# SuperTester-v07.net
KiCad netlist of a schematic drawn in EAGLE
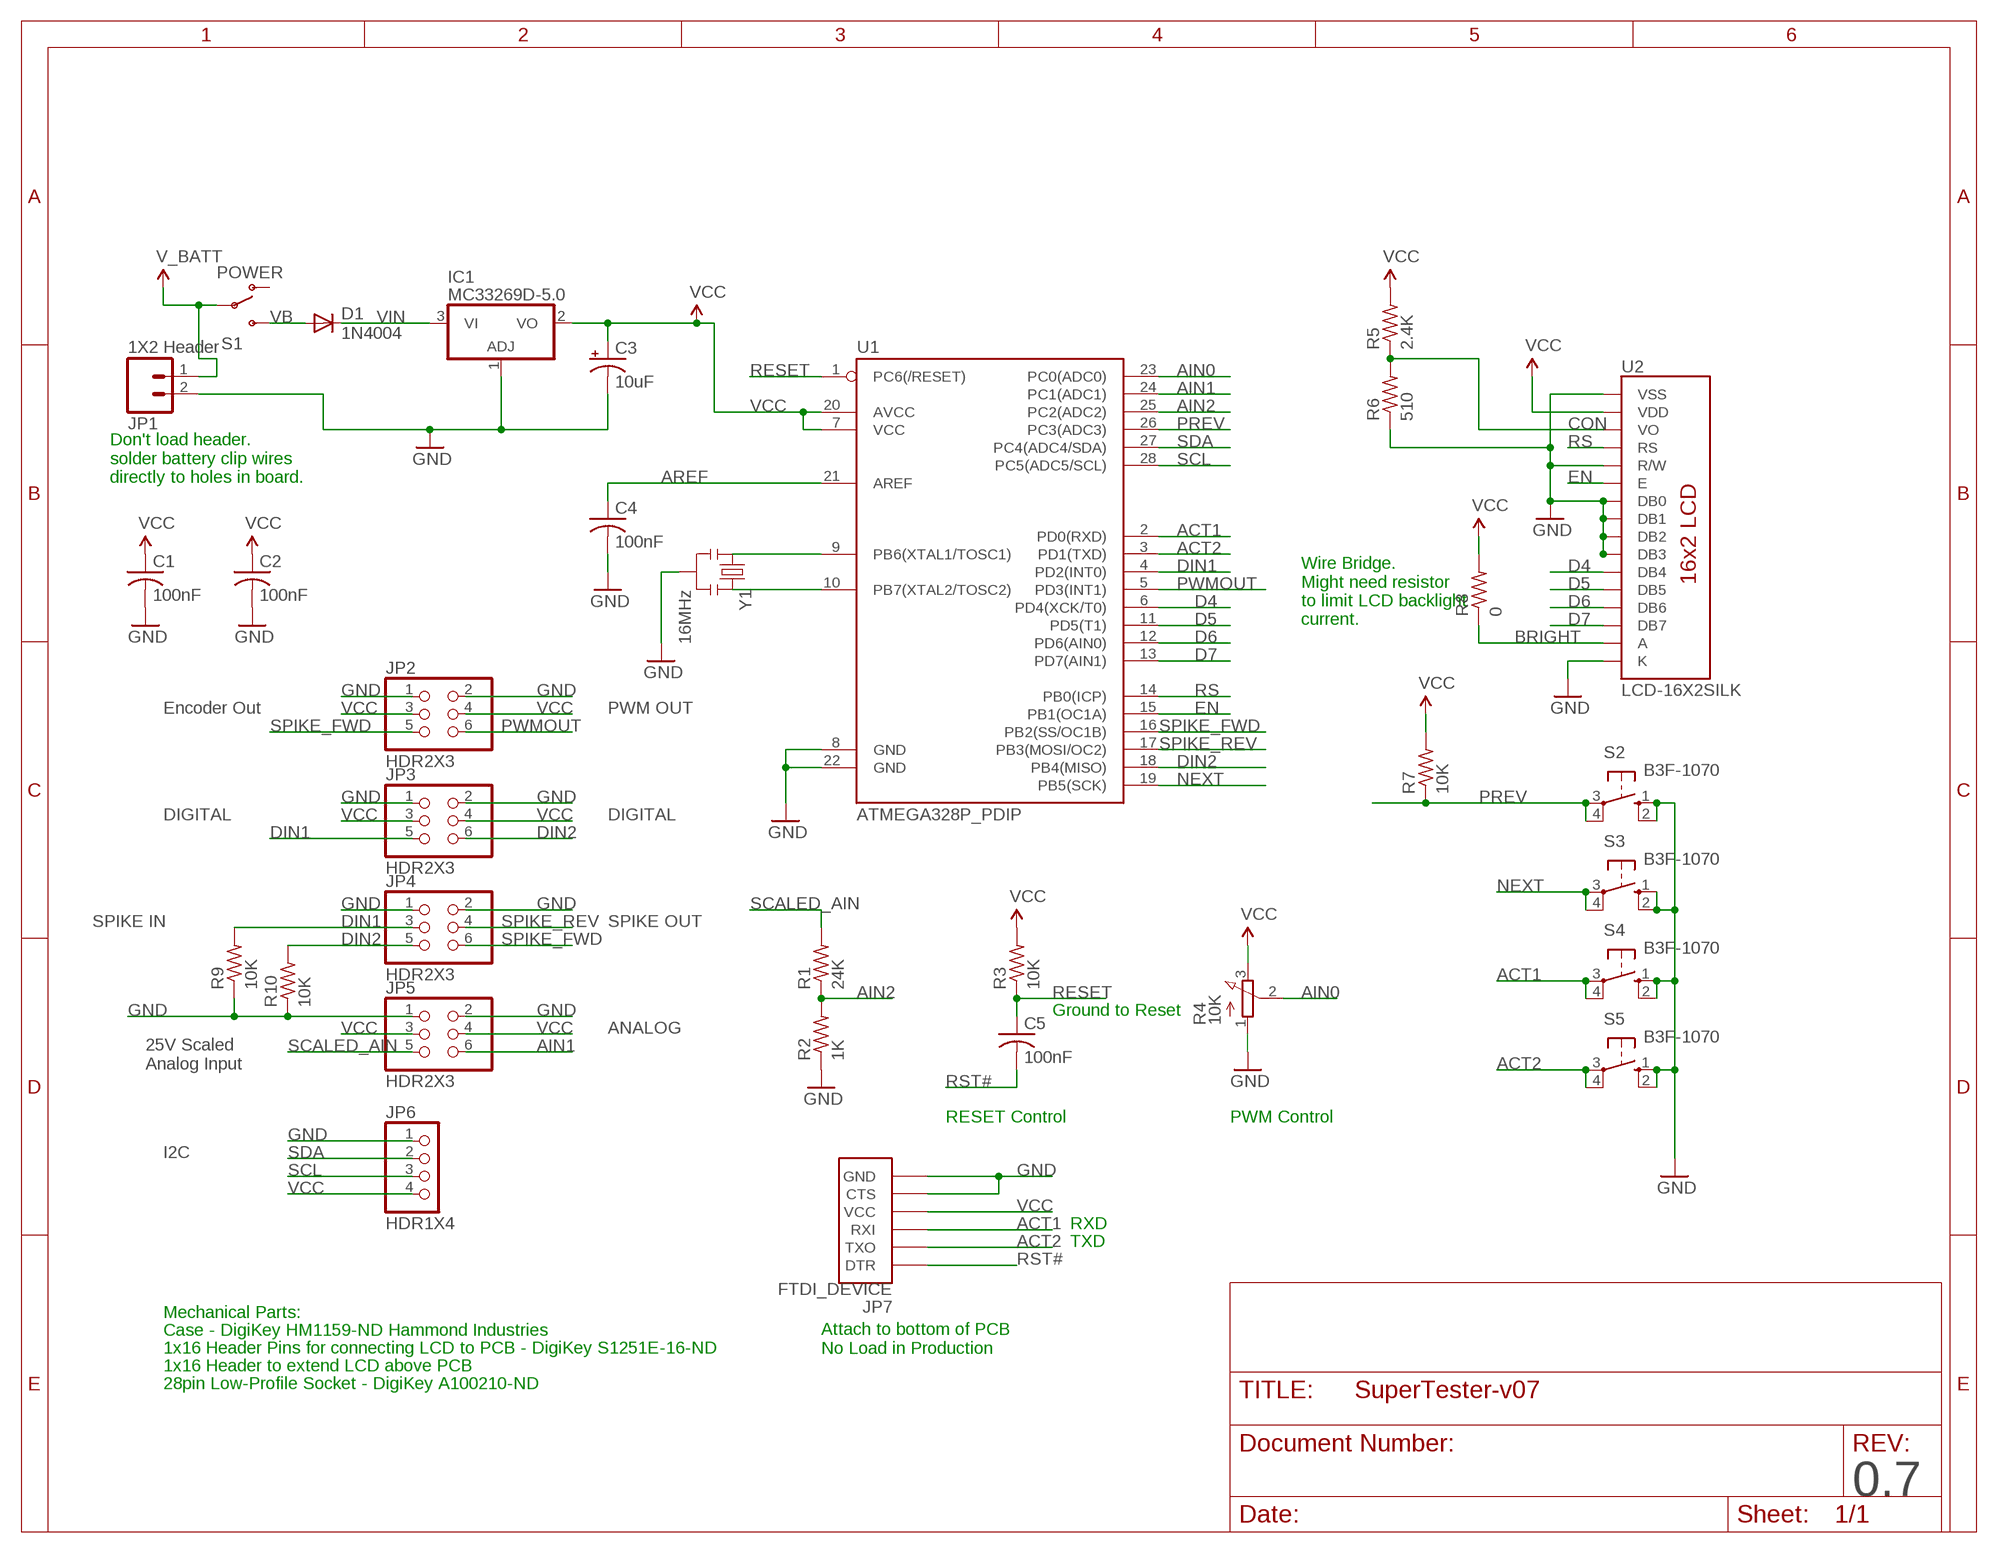
[diagram p0: schematic, sheet 1]

(export (version "E")
  (design (tool "Eeschema 10.0.6"))
  (components
    (comp (ref "C1")
      (value "100nF")
      (footprint "eagle-import:C025-025X050")
      (fields (field (name "PARTNO") "SR295E104MAR"))
      (libsource (lib "eagle-import") (part "C-US025-025X050"))
    )
    (comp (ref "C2")
      (value "100nF")
      (footprint "eagle-import:C025-025X050")
      (fields (field (name "PARTNO") "SR295E104MAR"))
      (libsource (lib "eagle-import") (part "C-US025-025X050"))
    )
    (comp (ref "C3")
      (value "10uF")
      (footprint "eagle-import:E2,5-6E")
      (fields (field (name "PARTNO") "TAP106M025SCS"))
      (libsource (lib "eagle-import") (part "CPOL-USE2,5-6E"))
    )
    (comp (ref "C4")
      (value "100nF")
      (footprint "eagle-import:C025-025X050")
      (fields (field (name "PARTNO") "SR295E104MAR"))
      (libsource (lib "eagle-import") (part "C-US025-025X050"))
    )
    (comp (ref "C5")
      (value "100nF")
      (footprint "eagle-import:C025-025X050")
      (fields (field (name "PARTNO") "SR295E104MAR"))
      (libsource (lib "eagle-import") (part "C-US025-025X050"))
    )
    (comp (ref "D1")
      (value "1N4004")
      (footprint "eagle-import:DO41-10")
      (fields (field (name "PARTNO") "1N4004GP-E3/54"))
      (libsource (lib "eagle-import") (part "1N4004"))
    )
    (comp (ref "IC1")
      (value "MC33269D-5.0")
      (footprint "eagle-import:DPACK")
      (fields (field (name "PARTNO") "MC33269DTRK-5.0G"))
      (libsource (lib "eagle-import") (part "MC33269?D-5.0"))
    )
    (comp (ref "JP1")
      (value "1X2 Header")
      (footprint "eagle-import:1X02")
      (fields (field (name "PARTNO") "640456-2"))
      (libsource (lib "eagle-import") (part "M02PTH"))
    )
    (comp (ref "JP2")
      (value "HDR2X3")
      (footprint "eagle-import:2X03_90")
      (fields (field (name "PARTNO") "68021-206HLF"))
      (libsource (lib "eagle-import") (part "PINHD-2X3/90"))
    )
    (comp (ref "JP3")
      (value "HDR2X3")
      (footprint "eagle-import:2X03_90")
      (fields (field (name "PARTNO") "68021-206HLF"))
      (libsource (lib "eagle-import") (part "PINHD-2X3/90"))
    )
    (comp (ref "JP4")
      (value "HDR2X3")
      (footprint "eagle-import:2X03_90")
      (fields (field (name "PARTNO") "68021-206HLF"))
      (libsource (lib "eagle-import") (part "PINHD-2X3/90"))
    )
    (comp (ref "JP5")
      (value "HDR2X3")
      (footprint "eagle-import:2X03_90")
      (fields (field (name "PARTNO") "68021-206HLF"))
      (libsource (lib "eagle-import") (part "PINHD-2X3/90"))
    )
    (comp (ref "JP6")
      (value "HDR1X4")
      (footprint "eagle-import:1X04_90")
      (fields (field (name "PARTNO") "68016-204HLF"))
      (libsource (lib "eagle-import") (part "PINHD-1X4/90"))
    )
    (comp (ref "JP7")
      (value "FTDI_DEVICE")
      (footprint "eagle-import:FTDI_DEVICE_SIDE")
      (fields (field (name "PARTNO") "826926-6"))
      (libsource (lib "eagle-import") (part "FTDI_DEVICE"))
    )
    (comp (ref "R1")
      (value "24K")
      (footprint "eagle-import:0207_7")
      (fields (field (name "PARTNO") "CFR-12JB-52-24K"))
      (libsource (lib "eagle-import") (part "R-US_0207/7"))
    )
    (comp (ref "R2")
      (value "1K")
      (footprint "eagle-import:0207_7")
      (fields (field (name "PARTNO") "CFR-12JB-52-1K"))
      (libsource (lib "eagle-import") (part "R-US_0207/7"))
    )
    (comp (ref "R3")
      (value "10K")
      (footprint "eagle-import:0207_7")
      (fields (field (name "PARTNO") "CFR-12JB-52-10K"))
      (libsource (lib "eagle-import") (part "R-US_0207/7"))
    )
    (comp (ref "R4")
      (value "10K")
      (footprint "eagle-import:EVUF")
      (fields (field (name "PARTNO") "EVU-F3AF30B14"))
      (libsource (lib "eagle-import") (part "EVUAF3"))
    )
    (comp (ref "R5")
      (value "2.4K")
      (footprint "eagle-import:0207_7")
      (fields (field (name "PARTNO") "CFR-12JB-52-2K4"))
      (libsource (lib "eagle-import") (part "R-US_0207/7"))
    )
    (comp (ref "R6")
      (value "510")
      (footprint "eagle-import:0207_7")
      (fields (field (name "PARTNO") "CFR-12JB-52-510R"))
      (libsource (lib "eagle-import") (part "R-US_0207/7"))
    )
    (comp (ref "R7")
      (value "10K")
      (footprint "eagle-import:0207_7")
      (fields (field (name "PARTNO") "CFR-12JB-52-10K"))
      (libsource (lib "eagle-import") (part "R-US_0207/7"))
    )
    (comp (ref "R8")
      (value "0")
      (footprint "eagle-import:0207_7")
      (fields (field (name "PARTNO") "ZOR-12-B-52-0R"))
      (libsource (lib "eagle-import") (part "R-US_0207/7"))
    )
    (comp (ref "R9")
      (value "10K")
      (footprint "eagle-import:0207_7")
      (fields (field (name "PARTNO") "CFR-12JB-52-10K"))
      (libsource (lib "eagle-import") (part "R-US_0207/7"))
    )
    (comp (ref "R10")
      (value "10K")
      (footprint "eagle-import:0207_7")
      (fields (field (name "PARTNO") "CFR-12JB-52-10K"))
      (libsource (lib "eagle-import") (part "R-US_0207/7"))
    )
    (comp (ref "S1")
      (value "POWER")
      (footprint "eagle-import:SWITCH-SPDT")
      (fields (field (name "PARTNO") "EG1218"))
      (libsource (lib "eagle-import") (part "SWITCH-SPDTPTH"))
    )
    (comp (ref "S2")
      (value "B3F-1070")
      (footprint "eagle-import:B3F-10XX")
      (fields (field (name "MPN") "B3F-1000"))
      (libsource (lib "eagle-import") (part "10-XX"))
    )
    (comp (ref "S3")
      (value "B3F-1070")
      (footprint "eagle-import:B3F-10XX")
      (fields (field (name "MPN") "B3F-1000"))
      (libsource (lib "eagle-import") (part "10-XX"))
    )
    (comp (ref "S4")
      (value "B3F-1070")
      (footprint "eagle-import:B3F-10XX")
      (fields (field (name "MPN") "B3F-1000"))
      (libsource (lib "eagle-import") (part "10-XX"))
    )
    (comp (ref "S5")
      (value "B3F-1070")
      (footprint "eagle-import:B3F-10XX")
      (fields (field (name "MPN") "B3F-1000"))
      (libsource (lib "eagle-import") (part "10-XX"))
    )
    (comp (ref "U1")
      (value "ATMEGA328P_PDIP")
      (footprint "eagle-import:DIL28-3")
      (fields (field (name "PARTNO") "ATMEGA328P-PU"))
      (libsource (lib "eagle-import") (part "ATMEGA328P_PDIP"))
    )
    (comp (ref "U2")
      (value "LCD-16X2SILK")
      (footprint "eagle-import:LCD-16X2")
      (fields (field (name "PARTNO") "LCM-S01602DSF/A"))
      (libsource (lib "eagle-import") (part "LCD-16X2SILK"))
    )
    (comp (ref "Y1")
      (value "16MHz")
      (footprint "eagle-import:RESONATOR-PTH")
      (fields (field (name "PARTNO") "CSTLS16M0X53-B0"))
      (libsource (lib "eagle-import") (part "RESONATORPTH"))
    )
  )
  (nets
    (net (code "1") (name "/ACT1") (class "Default")
      (node (ref "JP7") (pin "P$3") (pinfunction "RXI_P$3") (pintype "bidirectional"))
      (node (ref "S4") (pin "3") (pinfunction "P_3") (pintype "passive"))
      (node (ref "S4") (pin "4") (pinfunction "P1_4") (pintype "passive"))
      (node (ref "U1") (pin "2") (pinfunction "PD0(RXD)_2") (pintype "bidirectional"))
    )
    (net (code "2") (name "/ACT2") (class "Default")
      (node (ref "JP7") (pin "P$2") (pinfunction "TXO_P$2") (pintype "bidirectional"))
      (node (ref "S5") (pin "3") (pinfunction "P_3") (pintype "passive"))
      (node (ref "S5") (pin "4") (pinfunction "P1_4") (pintype "passive"))
      (node (ref "U1") (pin "3") (pinfunction "PD1(TXD)_3") (pintype "bidirectional"))
    )
    (net (code "3") (name "/AIN0") (class "Default")
      (node (ref "R4") (pin "2") (pinfunction "S_2") (pintype "passive"))
      (node (ref "U1") (pin "23") (pinfunction "PC0(ADC0)_23") (pintype "bidirectional"))
    )
    (net (code "4") (name "/AIN1") (class "Default")
      (node (ref "JP5") (pin "6") (pinfunction "6_6") (pintype "passive"))
      (node (ref "U1") (pin "24") (pinfunction "PC1(ADC1)_24") (pintype "bidirectional"))
    )
    (net (code "5") (name "/AIN2") (class "Default")
      (node (ref "R1") (pin "1") (pinfunction "1_1") (pintype "passive"))
      (node (ref "R2") (pin "2") (pinfunction "2_2") (pintype "passive"))
      (node (ref "U1") (pin "25") (pinfunction "PC2(ADC2)_25") (pintype "bidirectional"))
    )
    (net (code "6") (name "/AREF") (class "Default")
      (node (ref "C4") (pin "1") (pinfunction "1_1") (pintype "passive"))
      (node (ref "U1") (pin "21") (pinfunction "AREF_21") (pintype "bidirectional"))
    )
    (net (code "7") (name "/BRIGHT") (class "Default")
      (node (ref "R8") (pin "1") (pinfunction "1_1") (pintype "passive"))
      (node (ref "U2") (pin "15") (pinfunction "A_15") (pintype "power_in"))
    )
    (net (code "8") (name "/CON") (class "Default")
      (node (ref "R5") (pin "1") (pinfunction "1_1") (pintype "passive"))
      (node (ref "R6") (pin "2") (pinfunction "2_2") (pintype "passive"))
      (node (ref "U2") (pin "3") (pinfunction "VO_3") (pintype "bidirectional"))
    )
    (net (code "9") (name "/D4") (class "Default")
      (node (ref "U1") (pin "6") (pinfunction "PD4(XCK/T0)_6") (pintype "bidirectional"))
      (node (ref "U2") (pin "11") (pinfunction "DB4_11") (pintype "bidirectional"))
    )
    (net (code "10") (name "/D5") (class "Default")
      (node (ref "U1") (pin "11") (pinfunction "PD5(T1)_11") (pintype "bidirectional"))
      (node (ref "U2") (pin "12") (pinfunction "DB5_12") (pintype "bidirectional"))
    )
    (net (code "11") (name "/D6") (class "Default")
      (node (ref "U1") (pin "12") (pinfunction "PD6(AIN0)_12") (pintype "bidirectional"))
      (node (ref "U2") (pin "13") (pinfunction "DB6_13") (pintype "bidirectional"))
    )
    (net (code "12") (name "/D7") (class "Default")
      (node (ref "U1") (pin "13") (pinfunction "PD7(AIN1)_13") (pintype "bidirectional"))
      (node (ref "U2") (pin "14") (pinfunction "DB7_14") (pintype "bidirectional"))
    )
    (net (code "13") (name "/DIN1") (class "Default")
      (node (ref "JP3") (pin "5") (pinfunction "5_5") (pintype "passive"))
      (node (ref "JP4") (pin "3") (pinfunction "3_3") (pintype "passive"))
      (node (ref "R9") (pin "2") (pinfunction "2_2") (pintype "passive"))
      (node (ref "U1") (pin "4") (pinfunction "PD2(INT0)_4") (pintype "bidirectional"))
    )
    (net (code "14") (name "/DIN2") (class "Default")
      (node (ref "JP3") (pin "6") (pinfunction "6_6") (pintype "passive"))
      (node (ref "JP4") (pin "5") (pinfunction "5_5") (pintype "passive"))
      (node (ref "R10") (pin "2") (pinfunction "2_2") (pintype "passive"))
      (node (ref "U1") (pin "18") (pinfunction "PB4(MISO)_18") (pintype "bidirectional"))
    )
    (net (code "15") (name "/EN") (class "Default")
      (node (ref "U1") (pin "15") (pinfunction "PB1(OC1A)_15") (pintype "bidirectional"))
      (node (ref "U2") (pin "6") (pinfunction "E_6") (pintype "input"))
    )
    (net (code "16") (name "/NEXT") (class "Default")
      (node (ref "S3") (pin "3") (pinfunction "P_3") (pintype "passive"))
      (node (ref "S3") (pin "4") (pinfunction "P1_4") (pintype "passive"))
      (node (ref "U1") (pin "19") (pinfunction "PB5(SCK)_19") (pintype "bidirectional"))
    )
    (net (code "17") (name "/PREV") (class "Default")
      (node (ref "R7") (pin "1") (pinfunction "1_1") (pintype "passive"))
      (node (ref "S2") (pin "3") (pinfunction "P_3") (pintype "passive"))
      (node (ref "S2") (pin "4") (pinfunction "P1_4") (pintype "passive"))
      (node (ref "U1") (pin "26") (pinfunction "PC3(ADC3)_26") (pintype "bidirectional"))
    )
    (net (code "18") (name "/PWMOUT") (class "Default")
      (node (ref "JP2") (pin "6") (pinfunction "6_6") (pintype "passive"))
      (node (ref "U1") (pin "5") (pinfunction "PD3(INT1)_5") (pintype "bidirectional"))
    )
    (net (code "19") (name "/RESET") (class "Default")
      (node (ref "C5") (pin "1") (pinfunction "1_1") (pintype "passive"))
      (node (ref "R3") (pin "1") (pinfunction "1_1") (pintype "passive"))
      (node (ref "U1") (pin "1") (pinfunction "PC6(/RESET)_1") (pintype "bidirectional"))
    )
    (net (code "20") (name "/RS") (class "Default")
      (node (ref "U1") (pin "14") (pinfunction "PB0(ICP)_14") (pintype "bidirectional"))
      (node (ref "U2") (pin "4") (pinfunction "RS_4") (pintype "input"))
    )
    (net (code "21") (name "/RST#") (class "Default")
      (node (ref "C5") (pin "2") (pinfunction "2_2") (pintype "passive"))
      (node (ref "JP7") (pin "P$1") (pinfunction "DTR_P$1") (pintype "bidirectional"))
    )
    (net (code "22") (name "/SCALED_AIN") (class "Default")
      (node (ref "JP5") (pin "5") (pinfunction "5_5") (pintype "passive"))
      (node (ref "R1") (pin "2") (pinfunction "2_2") (pintype "passive"))
    )
    (net (code "23") (name "/SCL") (class "Default")
      (node (ref "JP6") (pin "3") (pinfunction "3_3") (pintype "passive"))
      (node (ref "U1") (pin "28") (pinfunction "PC5(ADC5/SCL)_28") (pintype "bidirectional"))
    )
    (net (code "24") (name "/SDA") (class "Default")
      (node (ref "JP6") (pin "2") (pinfunction "2_2") (pintype "passive"))
      (node (ref "U1") (pin "27") (pinfunction "PC4(ADC4/SDA)_27") (pintype "bidirectional"))
    )
    (net (code "25") (name "/SPIKE_FWD") (class "Default")
      (node (ref "JP2") (pin "5") (pinfunction "5_5") (pintype "passive"))
      (node (ref "JP4") (pin "6") (pinfunction "6_6") (pintype "passive"))
      (node (ref "U1") (pin "16") (pinfunction "PB2(SS/OC1B)_16") (pintype "bidirectional"))
    )
    (net (code "26") (name "/SPIKE_REV") (class "Default")
      (node (ref "JP4") (pin "4") (pinfunction "4_4") (pintype "passive"))
      (node (ref "U1") (pin "17") (pinfunction "PB3(MOSI/OC2)_17") (pintype "bidirectional"))
    )
    (net (code "27") (name "/VB") (class "Default")
      (node (ref "D1") (pin "A") (pinfunction "A_A") (pintype "passive"))
      (node (ref "S1") (pin "3") (pinfunction "S_3") (pintype "passive"))
    )
    (net (code "28") (name "/VIN") (class "Default")
      (node (ref "D1") (pin "C") (pinfunction "C_C") (pintype "passive"))
      (node (ref "IC1") (pin "3") (pinfunction "VI_3") (pintype "input"))
    )
    (net (code "29") (name "GND") (class "Default")
      (node (ref "C1") (pin "2") (pinfunction "2_2") (pintype "passive"))
      (node (ref "C2") (pin "2") (pinfunction "2_2") (pintype "passive"))
      (node (ref "C3") (pin "-") (pinfunction "-_-") (pintype "passive"))
      (node (ref "C4") (pin "2") (pinfunction "2_2") (pintype "passive"))
      (node (ref "IC1") (pin "1") (pinfunction "ADJ_1") (pintype "input"))
      (node (ref "JP1") (pin "2") (pinfunction "2_2") (pintype "passive"))
      (node (ref "JP2") (pin "1") (pinfunction "1_1") (pintype "passive"))
      (node (ref "JP2") (pin "2") (pinfunction "2_2") (pintype "passive"))
      (node (ref "JP3") (pin "1") (pinfunction "1_1") (pintype "passive"))
      (node (ref "JP3") (pin "2") (pinfunction "2_2") (pintype "passive"))
      (node (ref "JP4") (pin "1") (pinfunction "1_1") (pintype "passive"))
      (node (ref "JP4") (pin "2") (pinfunction "2_2") (pintype "passive"))
      (node (ref "JP5") (pin "1") (pinfunction "1_1") (pintype "passive"))
      (node (ref "JP5") (pin "2") (pinfunction "2_2") (pintype "passive"))
      (node (ref "JP6") (pin "1") (pinfunction "1_1") (pintype "passive"))
      (node (ref "JP7") (pin "P$5") (pinfunction "CTS_P$5") (pintype "bidirectional"))
      (node (ref "JP7") (pin "P$6") (pinfunction "GND_P$6") (pintype "bidirectional"))
      (node (ref "R10") (pin "1") (pinfunction "1_1") (pintype "passive"))
      (node (ref "R2") (pin "1") (pinfunction "1_1") (pintype "passive"))
      (node (ref "R4") (pin "1") (pinfunction "A_1") (pintype "passive"))
      (node (ref "R6") (pin "1") (pinfunction "1_1") (pintype "passive"))
      (node (ref "R9") (pin "1") (pinfunction "1_1") (pintype "passive"))
      (node (ref "S2") (pin "1") (pinfunction "S_1") (pintype "passive"))
      (node (ref "S2") (pin "2") (pinfunction "S1_2") (pintype "passive"))
      (node (ref "S3") (pin "1") (pinfunction "S_1") (pintype "passive"))
      (node (ref "S3") (pin "2") (pinfunction "S1_2") (pintype "passive"))
      (node (ref "S4") (pin "1") (pinfunction "S_1") (pintype "passive"))
      (node (ref "S4") (pin "2") (pinfunction "S1_2") (pintype "passive"))
      (node (ref "S5") (pin "1") (pinfunction "S_1") (pintype "passive"))
      (node (ref "S5") (pin "2") (pinfunction "S1_2") (pintype "passive"))
      (node (ref "U1") (pin "22") (pinfunction "GND_22") (pintype "bidirectional"))
      (node (ref "U1") (pin "8") (pinfunction "GND_8") (pintype "bidirectional"))
      (node (ref "U2") (pin "1") (pinfunction "VSS_1") (pintype "power_in"))
      (node (ref "U2") (pin "10") (pinfunction "DB3_10") (pintype "bidirectional"))
      (node (ref "U2") (pin "16") (pinfunction "K_16") (pintype "power_in"))
      (node (ref "U2") (pin "5") (pinfunction "R/W_5") (pintype "input"))
      (node (ref "U2") (pin "7") (pinfunction "DB0_7") (pintype "bidirectional"))
      (node (ref "U2") (pin "8") (pinfunction "DB1_8") (pintype "bidirectional"))
      (node (ref "U2") (pin "9") (pinfunction "DB2_9") (pintype "bidirectional"))
      (node (ref "Y1") (pin "2") (pinfunction "2_2") (pintype "passive"))
    )
    (net (code "30") (name "Net-(U1-PB6(XTAL1{slash}TOSC1))") (class "Default")
      (node (ref "U1") (pin "9") (pinfunction "PB6(XTAL1/TOSC1)_9") (pintype "bidirectional"))
      (node (ref "Y1") (pin "1") (pinfunction "1_1") (pintype "passive"))
    )
    (net (code "31") (name "Net-(U1-PB7(XTAL2{slash}TOSC2))") (class "Default")
      (node (ref "U1") (pin "10") (pinfunction "PB7(XTAL2/TOSC2)_10") (pintype "bidirectional"))
      (node (ref "Y1") (pin "3") (pinfunction "3_3") (pintype "passive"))
    )
    (net (code "32") (name "VCC") (class "Default")
      (node (ref "C1") (pin "1") (pinfunction "1_1") (pintype "passive"))
      (node (ref "C2") (pin "1") (pinfunction "1_1") (pintype "passive"))
      (node (ref "C3") (pin "+") (pinfunction "+_+") (pintype "passive"))
      (node (ref "IC1") (pin "2") (pinfunction "VO_2") (pintype "passive"))
      (node (ref "JP2") (pin "3") (pinfunction "3_3") (pintype "passive"))
      (node (ref "JP2") (pin "4") (pinfunction "4_4") (pintype "passive"))
      (node (ref "JP3") (pin "3") (pinfunction "3_3") (pintype "passive"))
      (node (ref "JP3") (pin "4") (pinfunction "4_4") (pintype "passive"))
      (node (ref "JP5") (pin "3") (pinfunction "3_3") (pintype "passive"))
      (node (ref "JP5") (pin "4") (pinfunction "4_4") (pintype "passive"))
      (node (ref "JP6") (pin "4") (pinfunction "4_4") (pintype "passive"))
      (node (ref "JP7") (pin "P$4") (pinfunction "VCC_P$4") (pintype "bidirectional"))
      (node (ref "R3") (pin "2") (pinfunction "2_2") (pintype "passive"))
      (node (ref "R4") (pin "3") (pinfunction "E_3") (pintype "passive"))
      (node (ref "R5") (pin "2") (pinfunction "2_2") (pintype "passive"))
      (node (ref "R7") (pin "2") (pinfunction "2_2") (pintype "passive"))
      (node (ref "R8") (pin "2") (pinfunction "2_2") (pintype "passive"))
      (node (ref "U1") (pin "20") (pinfunction "AVCC_20") (pintype "bidirectional"))
      (node (ref "U1") (pin "7") (pinfunction "VCC_7") (pintype "bidirectional"))
      (node (ref "U2") (pin "2") (pinfunction "VDD_2") (pintype "power_in"))
    )
    (net (code "33") (name "V_BATT") (class "Default")
      (node (ref "JP1") (pin "1") (pinfunction "1_1") (pintype "passive"))
      (node (ref "S1") (pin "2") (pinfunction "P_2") (pintype "passive"))
    )
    (net (code "34") (name "unconnected-(S1-O-Pad1)") (class "Default")
      (node (ref "S1") (pin "1") (pinfunction "O_1") (pintype "passive"))
    )
  )
)
